# power-slot.net
KiCad netlist of a schematic drawn in EAGLE
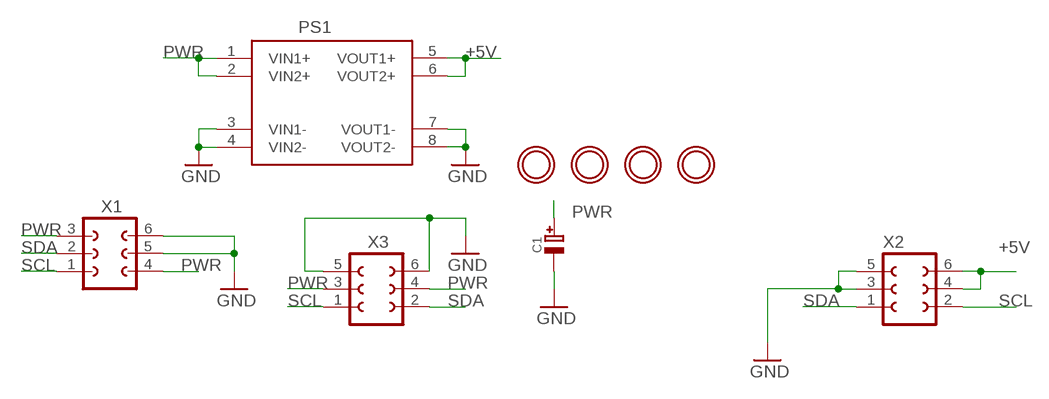
[diagram p0: schematic, sheet 1]

(export (version "E")
  (design (tool "Eeschema 10.0.6"))
  (components
    (comp (ref "C1")
      (value "CAP_ELECTROLYTICPTH_3.5MMGRID_8MMDIA")
      (footprint "eagle-import:CELEC_3.5MM_8MM")
      (libsource (lib "eagle-import") (part "CAP_ELECTROLYTICPTH_3.5MMGRID_8MMDIA"))
    )
    (comp (ref "PS1")
      (value "K8801MODULE")
      (footprint "eagle-import:K8801")
      (libsource (lib "eagle-import") (part "K8801MODULE"))
    )
    (comp (ref "U$1")
      (value "MOUNTINGHOLE2.5_THICK")
      (footprint "eagle-import:MOUNTINGHOLE_2.5_PLATED_THICK")
      (libsource (lib "eagle-import") (part "MOUNTINGHOLE2.5_THICK"))
    )
    (comp (ref "U$2")
      (value "MOUNTINGHOLE2.5_THICK")
      (footprint "eagle-import:MOUNTINGHOLE_2.5_PLATED_THICK")
      (libsource (lib "eagle-import") (part "MOUNTINGHOLE2.5_THICK"))
    )
    (comp (ref "U$3")
      (value "MOUNTINGHOLE2.5_THICK")
      (footprint "eagle-import:MOUNTINGHOLE_2.5_PLATED_THICK")
      (libsource (lib "eagle-import") (part "MOUNTINGHOLE2.5_THICK"))
    )
    (comp (ref "U$4")
      (value "MOUNTINGHOLE2.5_THICK")
      (footprint "eagle-import:MOUNTINGHOLE_2.5_PLATED_THICK")
      (libsource (lib "eagle-import") (part "MOUNTINGHOLE2.5_THICK"))
    )
    (comp (ref "X1")
      (value "CON-MA03-2MA03-2W")
      (footprint "eagle-import:MA03-2W")
      (libsource (lib "eagle-import") (part "CON-MA03-2MA03-2W"))
    )
    (comp (ref "X2")
      (value "CON-FE03-2CARDEDGE-0.1")
      (footprint "eagle-import:FE3-2-CARDEDGE-0.1")
      (libsource (lib "eagle-import") (part "CON-FE03-2CARDEDGE-0.1"))
    )
    (comp (ref "X3")
      (value "FE06-2W")
      (footprint "eagle-import:FE06-2W")
      (libsource (lib "eagle-import") (part "FE06-2W"))
    )
  )
  (nets
    (net (code "1") (name "/+5V") (class "Default")
      (node (ref "PS1") (pin "5") (pinfunction "VOUT1+_5") (pintype "bidirectional"))
      (node (ref "PS1") (pin "6") (pinfunction "VOUT2+_6") (pintype "bidirectional"))
      (node (ref "X2") (pin "4") (pinfunction "4_4") (pintype "passive"))
      (node (ref "X2") (pin "6") (pinfunction "6_6") (pintype "passive"))
    )
    (net (code "2") (name "/PWR") (class "Default")
      (node (ref "C1") (pin "+") (pinfunction "+_+") (pintype "passive"))
      (node (ref "PS1") (pin "1") (pinfunction "VIN1+_1") (pintype "bidirectional"))
      (node (ref "PS1") (pin "2") (pinfunction "VIN2+_2") (pintype "bidirectional"))
      (node (ref "X1") (pin "3") (pinfunction "3_3") (pintype "passive"))
      (node (ref "X1") (pin "4") (pinfunction "4_4") (pintype "passive"))
      (node (ref "X3") (pin "3") (pinfunction "3_3") (pintype "passive"))
      (node (ref "X3") (pin "4") (pinfunction "4_4") (pintype "passive"))
    )
    (net (code "3") (name "/SCL") (class "Default")
      (node (ref "X1") (pin "1") (pinfunction "1_1") (pintype "passive"))
      (node (ref "X2") (pin "2") (pinfunction "2_2") (pintype "passive"))
      (node (ref "X3") (pin "1") (pinfunction "1_1") (pintype "passive"))
    )
    (net (code "4") (name "/SDA") (class "Default")
      (node (ref "X1") (pin "2") (pinfunction "2_2") (pintype "passive"))
      (node (ref "X2") (pin "1") (pinfunction "1_1") (pintype "passive"))
      (node (ref "X3") (pin "2") (pinfunction "2_2") (pintype "passive"))
    )
    (net (code "5") (name "GND") (class "Default")
      (node (ref "C1") (pin "-") (pinfunction "-_-") (pintype "passive"))
      (node (ref "PS1") (pin "3") (pinfunction "VIN1-_3") (pintype "bidirectional"))
      (node (ref "PS1") (pin "4") (pinfunction "VIN2-_4") (pintype "bidirectional"))
      (node (ref "PS1") (pin "7") (pinfunction "VOUT1-_7") (pintype "bidirectional"))
      (node (ref "PS1") (pin "8") (pinfunction "VOUT2-_8") (pintype "bidirectional"))
      (node (ref "X1") (pin "5") (pinfunction "5_5") (pintype "passive"))
      (node (ref "X1") (pin "6") (pinfunction "6_6") (pintype "passive"))
      (node (ref "X2") (pin "3") (pinfunction "3_3") (pintype "passive"))
      (node (ref "X2") (pin "5") (pinfunction "5_5") (pintype "passive"))
      (node (ref "X3") (pin "5") (pinfunction "5_5") (pintype "passive"))
      (node (ref "X3") (pin "6") (pinfunction "6_6") (pintype "passive"))
    )
  )
)
